# cat4101-bare.net
KiCad netlist of a schematic drawn in EAGLE
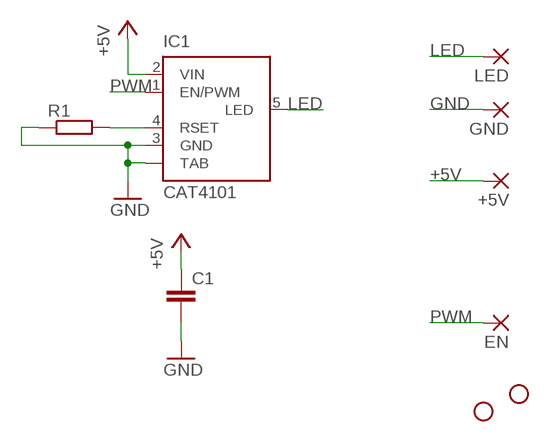
[diagram p0: schematic, sheet 1]

(export (version "E")
  (design (tool "Eeschema 10.0.6"))
  (components
    (comp (ref "+5V")
      (value "SMD2")
      (footprint "eagle-import:SMD1,27-2,54")
      (libsource (lib "eagle-import") (part "SMD2"))
    )
    (comp (ref "C1")
      (value "C-EUC0805K")
      (footprint "eagle-import:C0805K")
      (libsource (lib "eagle-import") (part "C-EUC0805K"))
    )
    (comp (ref "EN")
      (value "SMD2")
      (footprint "eagle-import:SMD1,27-2,54")
      (libsource (lib "eagle-import") (part "SMD2"))
    )
    (comp (ref "GND")
      (value "SMD5")
      (footprint "eagle-import:SMD2,54-5,08")
      (libsource (lib "eagle-import") (part "SMD5"))
    )
    (comp (ref "IC1")
      (value "CAT4101")
      (footprint "eagle-import:TO263_5")
      (fields (field (name "MPN") "CAT4101TV-T75"))
      (libsource (lib "eagle-import") (part "CAT4101"))
    )
    (comp (ref "JP1")
      (value "STAND-OFF")
      (footprint "eagle-import:STAND-OFF")
      (libsource (lib "eagle-import") (part "STAND-OFF"))
    )
    (comp (ref "JP2")
      (value "STAND-OFF")
      (footprint "eagle-import:STAND-OFF")
      (libsource (lib "eagle-import") (part "STAND-OFF"))
    )
    (comp (ref "LED")
      (value "SMD5")
      (footprint "eagle-import:SMD2,54-5,08")
      (libsource (lib "eagle-import") (part "SMD5"))
    )
    (comp (ref "R1")
      (value "R-EU_R0805")
      (footprint "eagle-import:R0805")
      (libsource (lib "eagle-import") (part "R-EU_R0805"))
    )
  )
  (nets
    (net (code "1") (name "+5V") (class "Default")
      (node (ref "+5V") (pin "1") (pinfunction "P_1") (pintype "passive"))
      (node (ref "C1") (pin "1") (pinfunction "1_1") (pintype "passive"))
      (node (ref "IC1") (pin "2") (pinfunction "VIN_2") (pintype "input"))
    )
    (net (code "2") (name "/LED") (class "Default")
      (node (ref "IC1") (pin "5") (pinfunction "LED_5") (pintype "power_in"))
      (node (ref "LED") (pin "1") (pinfunction "P_1") (pintype "passive"))
    )
    (net (code "3") (name "/PWM") (class "Default")
      (node (ref "EN") (pin "1") (pinfunction "P_1") (pintype "passive"))
      (node (ref "IC1") (pin "1") (pinfunction "EN/PWM_1") (pintype "input"))
    )
    (net (code "4") (name "GND") (class "Default")
      (node (ref "C1") (pin "2") (pinfunction "2_2") (pintype "passive"))
      (node (ref "GND") (pin "1") (pinfunction "P_1") (pintype "passive"))
      (node (ref "IC1") (pin "3") (pinfunction "GND_3") (pintype "power_in"))
      (node (ref "IC1") (pin "TAB") (pinfunction "TAB_TAB") (pintype "passive"))
      (node (ref "R1") (pin "1") (pinfunction "1_1") (pintype "passive"))
    )
    (net (code "5") (name "Net-(IC1-RSET)") (class "Default")
      (node (ref "IC1") (pin "4") (pinfunction "RSET_4") (pintype "input"))
      (node (ref "R1") (pin "2") (pinfunction "2_2") (pintype "passive"))
    )
  )
)
